# POWER.net
KiCad netlist of a schematic drawn in Altium Designer
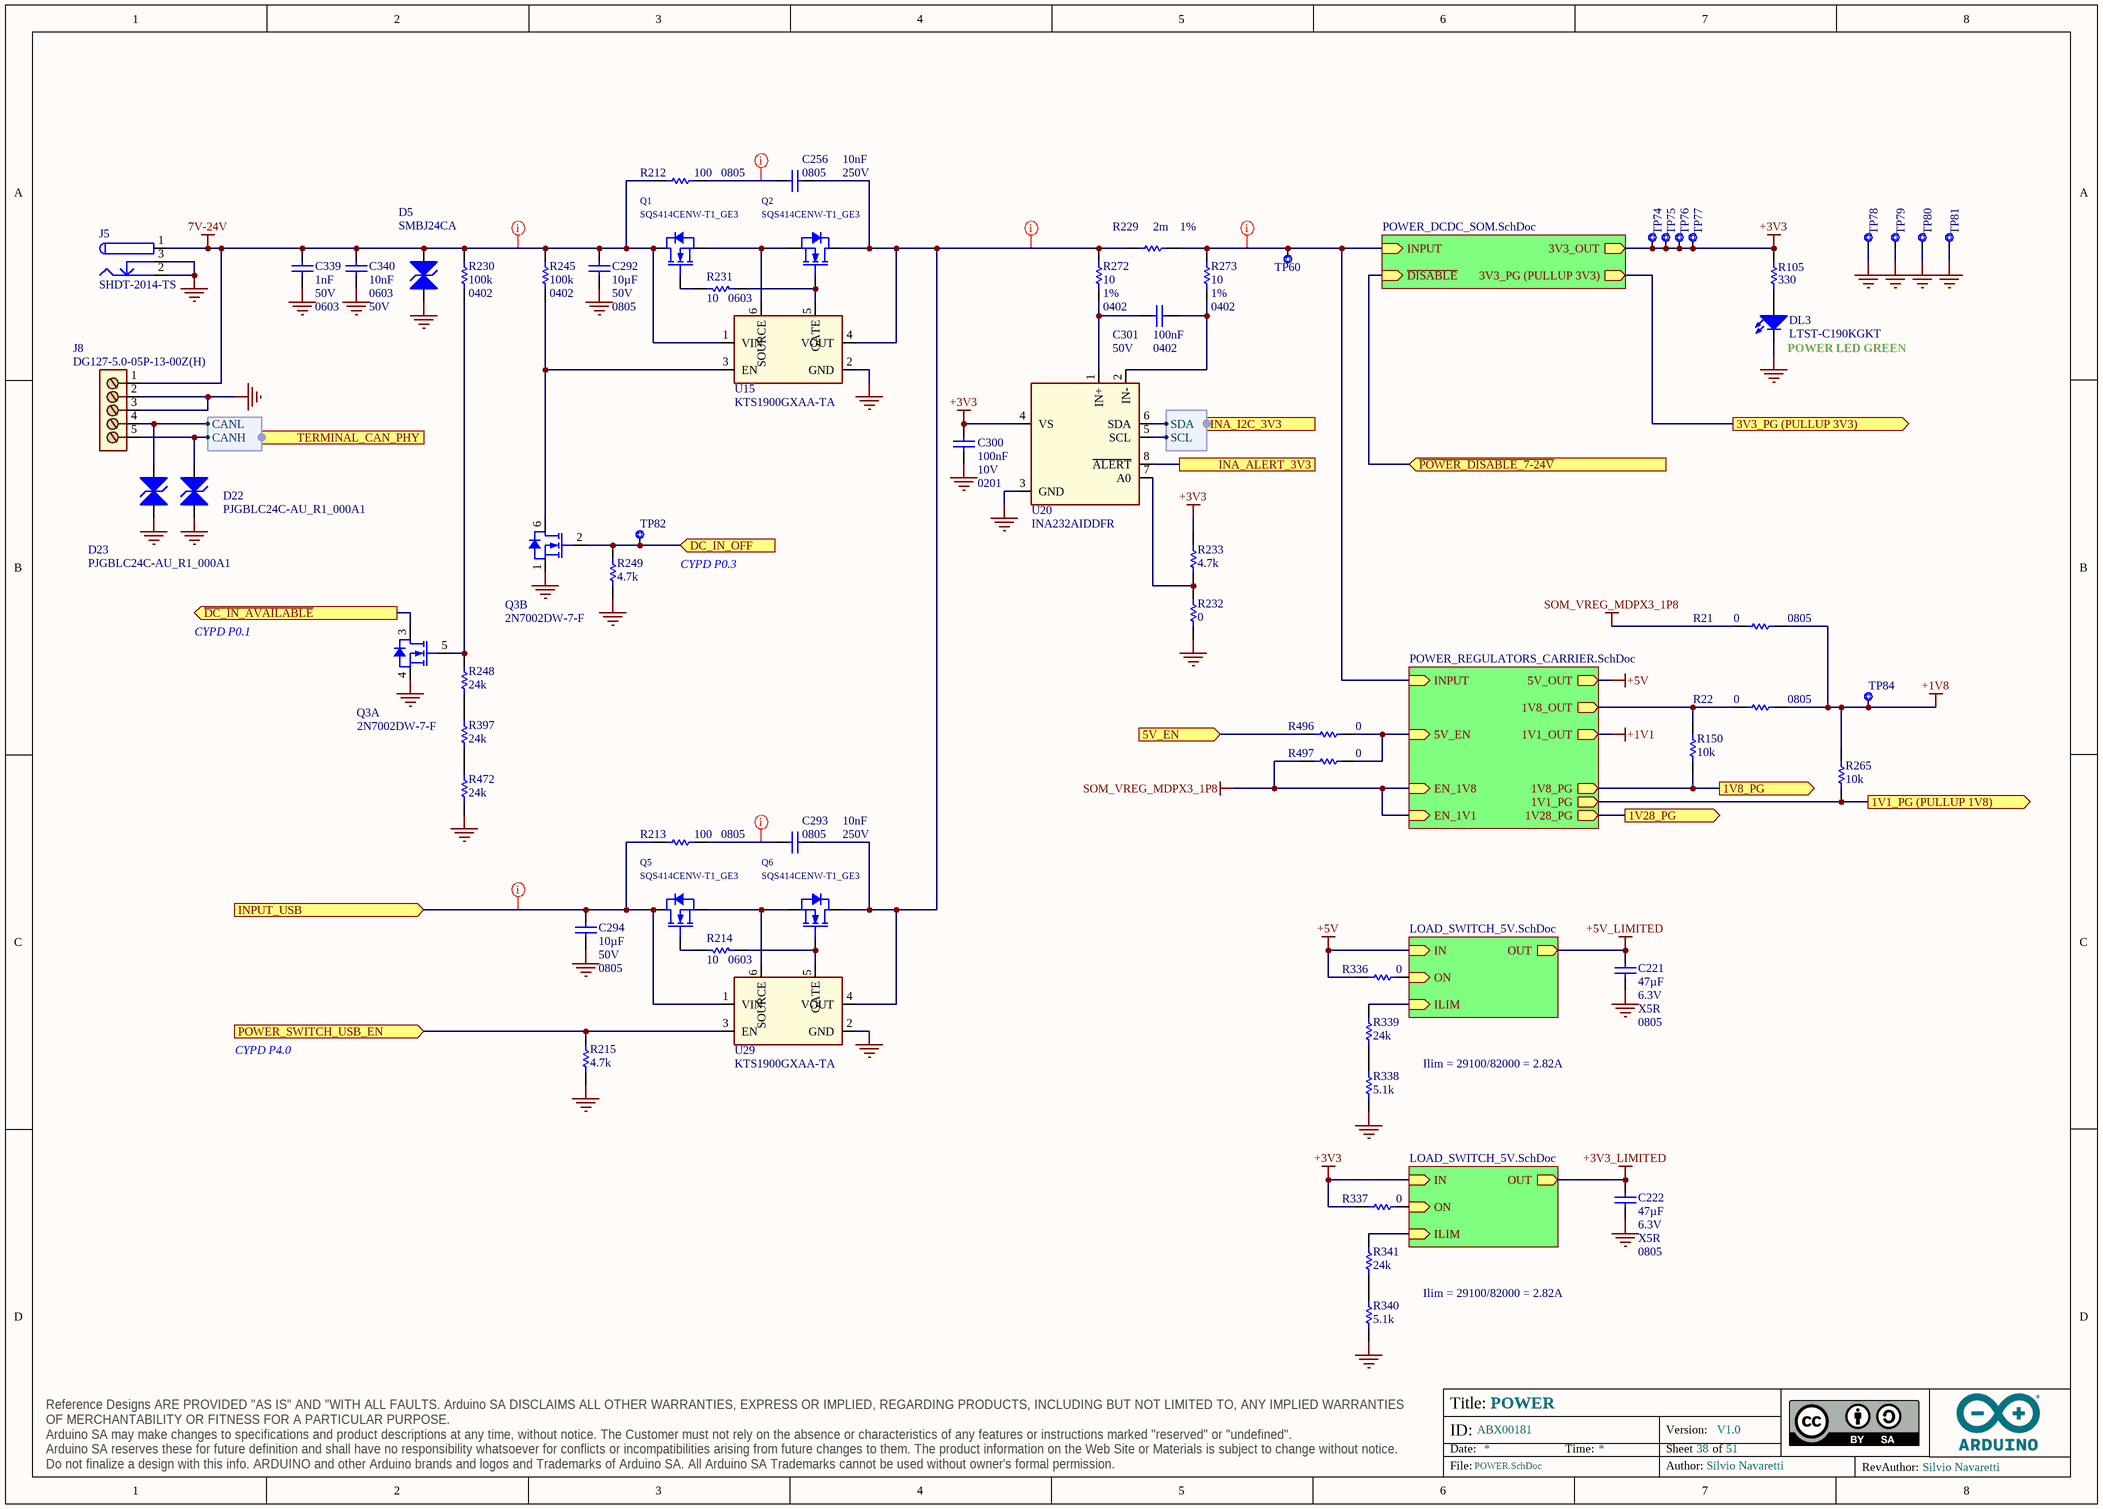
[diagram p0: POWER.SchDoc]

(export (version "E")
  (design (tool "Eeschema 10.0.6"))
  (components
    (comp (ref "C221")
      (value "47µF")
      (footprint "CAP-0805")
      (description "CAP CHIP 0805 47uF 20% 6.3V X5R")
      (fields
        (field (name "VOLTAGE") "6.3V")
        (field (name "DIELECTRIC") "X5R")
        (field (name "TOLERANCE") "20%")
        (field (name "CASE CODE (IMPERIAL)") "0805")
        (field (name "MANUFACTURER") "KEMET")
      )
      (libsource (lib "Clean") (part "CAP"))
    )
    (comp (ref "C222")
      (value "47µF")
      (footprint "CAP-0805")
      (description "CAP CHIP 0805 47uF 20% 6.3V X5R")
      (fields
        (field (name "VOLTAGE") "6.3V")
        (field (name "DIELECTRIC") "X5R")
        (field (name "TOLERANCE") "20%")
        (field (name "CASE CODE (IMPERIAL)") "0805")
        (field (name "MANUFACTURER") "KEMET")
      )
      (libsource (lib "Clean") (part "CAP"))
    )
    (comp (ref "C256")
      (value "10nF")
      (footprint "CAP-0805")
      (description "CAP CHIP 0805 10nF 250V X7R")
      (fields
        (field (name "CASE CODE (IMPERIAL)") "0805")
        (field (name "PART NUMBER") "GRM21BR72E103KW03L")
        (field (name "TOLERANCE") "10%")
        (field (name "VOLTAGE") "250V")
      )
      (libsource (lib "Clean") (part "CAP"))
    )
    (comp (ref "C292")
      (value "10µF")
      (footprint "CAP-0805")
      (description "CAP CHIP 0805 10uF 20% 50V X5R")
      (fields
        (field (name "VOLTAGE") "50V")
        (field (name "PART NUMBER") "GRM21BR61H106ME43L")
        (field (name "CASE CODE (IMPERIAL)") "0805")
        (field (name "MANUFACTURER") "Murata Electronics")
      )
      (libsource (lib "Clean") (part "CAP"))
    )
    (comp (ref "C293")
      (value "10nF")
      (footprint "CAP-0805")
      (description "CAP CHIP 0805 10nF 250V X7R")
      (fields
        (field (name "CASE CODE (IMPERIAL)") "0805")
        (field (name "PART NUMBER") "GRM21BR72E103KW03L")
        (field (name "TOLERANCE") "10%")
        (field (name "VOLTAGE") "250V")
      )
      (libsource (lib "Clean") (part "CAP"))
    )
    (comp (ref "C294")
      (value "10µF")
      (footprint "CAP-0805")
      (description "CAP CHIP 0805 10uF 20% 50V X5R")
      (fields
        (field (name "VOLTAGE") "50V")
        (field (name "PART NUMBER") "GRM21BR61H106ME43L")
        (field (name "CASE CODE (IMPERIAL)") "0805")
        (field (name "MANUFACTURER") "Murata Electronics")
      )
      (libsource (lib "Clean") (part "CAP"))
    )
    (comp (ref "C300")
      (value "100nF")
      (footprint "CAP-0201")
      (description "CAP CHIP 0201 100nF 10% 10V X5R")
      (fields
        (field (name "PART NUMBER") "CL03A104KP3NNNC")
        (field (name "MANUFACTURER") "Samsung Electro-Mechanics")
        (field (name "VOLTAGE") "10V")
        (field (name "CASE CODE (IMPERIAL)") "0201")
      )
      (libsource (lib "Clean") (part "CAP"))
    )
    (comp (ref "C301")
      (value "100nF")
      (footprint "CAP-0402")
      (description "CAP CHIP 0402 100nF 10% 50V X5R")
      (fields
        (field (name "MANUFACTURER") "Murata")
        (field (name "PART NUMBER") "GRM155R61H104KE19D")
        (field (name "VOLTAGE") "50V")
        (field (name "CASE CODE (IMPERIAL)") "0402")
      )
      (libsource (lib "Clean") (part "CAP"))
    )
    (comp (ref "C339")
      (value "1nF")
      (footprint "CAP-0603")
      (description "CAP CHIP 0603 1nF 10% 50V X7R")
      (fields
        (field (name "VOLTAGE") "50V")
        (field (name "TOLERANCE") "10%")
        (field (name "PART NUMBER") "CL10B102KB8WPNC")
        (field (name "CASE CODE (IMPERIAL)") "0603")
      )
      (libsource (lib "Clean") (part "CAP"))
    )
    (comp (ref "C340")
      (value "10nF")
      (footprint "CAP-0603")
      (description "CAP CHIP 0603 10nF 10% 50V X7R")
      (fields
        (field (name "CASE CODE (IMPERIAL)") "0603")
        (field (name "PART NUMBER") "0603B103K500CT")
        (field (name "TOLERANCE") "10%")
        (field (name "VOLTAGE") "50V")
      )
      (libsource (lib "Clean") (part "CAP"))
    )
    (comp (ref "D5")
      (value "SMBJ24CA")
      (footprint "SMB_NOPOLARITY")
      (description "TVS BIDIRECTIONAL SMD Vr 24V, Vbr min 26.7V, 600W, SMB")
      (fields (field (name "MANUFACTURER") "Littlefuse"))
      (libsource (lib "Clean") (part "Diode TVS"))
    )
    (comp (ref "D22")
      (value "PJGBLC24C-AU_R1_000A1")
      (footprint "SOD323 NO POLARITY")
      (description "TVS BIDIRECTIONAL SMD Vr 24V, Vbr min 27.27V, 350W, SOD-323")
      (libsource (lib "Clean") (part "Diode TVS"))
    )
    (comp (ref "D23")
      (value "PJGBLC24C-AU_R1_000A1")
      (footprint "SOD323 NO POLARITY")
      (description "TVS BIDIRECTIONAL SMD Vr 24V, Vbr min 27.27V, 350W, SOD-323")
      (libsource (lib "Clean") (part "Diode TVS"))
    )
    (comp (ref "DL3")
      (value "LTST-C190KGKT")
      (footprint "LEDC1608X80N-AK")
      (description "LED SMD 0603 GREEN/568 15mcd 120^")
      (fields (field (name "MANUFACTURER") "Liteon"))
      (libsource (lib "Clean") (part "LED"))
    )
    (comp (ref "J5")
      (value "SHDT-2014-TS")
      (footprint "SHDT-2014-TS")
      (description "CONN PWR JACK TH 2.1X5.5mm 1.6mm PCB")
      (fields (field (name "MANUFACTURER") "POWERWAY"))
      (libsource (lib "Clean") (part "SHDT-2014-TS"))
    )
    (comp (ref "J8")
      (value "DG127-5.0-05P-13-00Z(H)")
      (footprint "DG127-5.0-05P-13-00Z(H)")
      (description "CONN SCREW TERMINAL 5 POS pitch 5mm height 13.6mm BLACK")
      (fields (field (name "MANUFACTURER") "Degson"))
      (libsource (lib "Clean") (part "DG127-5.0-05P-13-00Z(H)"))
    )
    (comp (ref "Q1")
      (value "SQS414CENW-T1_GE3")
      (footprint "SQS414CENW-T1_GE3")
      (description "MOSFET N-CH 60V 18A PowerPAK 1212-8W 3.3x3.3mm")
      (fields (field (name "MANUFACTURER") "Vishay"))
      (libsource (lib "Clean") (part "SQS414CENW-T1_GE3"))
    )
    (comp (ref "Q2")
      (value "SQS414CENW-T1_GE3")
      (footprint "SQS414CENW-T1_GE3")
      (description "MOSFET N-CH 60V 18A PowerPAK 1212-8W 3.3x3.3mm")
      (fields (field (name "MANUFACTURER") "Vishay"))
      (libsource (lib "Clean") (part "SQS414CENW-T1_GE3"))
    )
    (comp (ref "Q3")
      (value "2N7002DW-7-F")
      (footprint "SOT363")
      (description "MOSFET 2N-CH 60V 0.32A SOT363")
      (fields (field (name "MANUFACTURER") "Diodes Inc.") (field (name "PART NUMBER") "2N7002DW-7-F"))
      (libsource (lib "Clean") (part "2N7002DW-7-F"))
    )
    (comp (ref "Q5")
      (value "SQS414CENW-T1_GE3")
      (footprint "SQS414CENW-T1_GE3")
      (description "MOSFET N-CH 60V 18A PowerPAK 1212-8W 3.3x3.3mm")
      (fields (field (name "MANUFACTURER") "Vishay"))
      (libsource (lib "Clean") (part "SQS414CENW-T1_GE3"))
    )
    (comp (ref "Q6")
      (value "SQS414CENW-T1_GE3")
      (footprint "SQS414CENW-T1_GE3")
      (description "MOSFET N-CH 60V 18A PowerPAK 1212-8W 3.3x3.3mm")
      (fields (field (name "MANUFACTURER") "Vishay"))
      (libsource (lib "Clean") (part "SQS414CENW-T1_GE3"))
    )
    (comp (ref "R21")
      (value "0")
      (footprint "RES-0805")
      (description "RES CHIP 0805 0R 1% 1/8W")
      (fields
        (field (name "POWER") "125mW")
        (field (name "PART NUMBER") "RC0805FR-070RL")
        (field (name "CASE CODE (IMPERIAL)") "0805")
      )
      (libsource (lib "Clean") (part "RES"))
    )
    (comp (ref "R22")
      (value "0")
      (footprint "RES-0805")
      (description "RES CHIP 0805 0R 1% 1/8W")
      (fields
        (field (name "POWER") "125mW")
        (field (name "PART NUMBER") "RC0805FR-070RL")
        (field (name "CASE CODE (IMPERIAL)") "0805")
      )
      (libsource (lib "Clean") (part "RES"))
    )
    (comp (ref "R105")
      (value "330")
      (footprint "RES-0201")
      (description "RES CHIP 0201 330R 1% 1/20W")
      (fields (field (name "MANUFACTURER") "Yageo") (field (name "POWER") "50mW"))
      (libsource (lib "Clean") (part "RES"))
    )
    (comp (ref "R150")
      (value "10k")
      (footprint "RES-0201")
      (description "RES CHIP 0201 10k 1% 1/20W")
      (fields (field (name "POWER") "50mW") (field (name "TOLERANCE") "1%"))
      (libsource (lib "Clean") (part "RES"))
    )
    (comp (ref "R212")
      (value "100")
      (footprint "RES-0805")
      (description "RES CHIP 0805 100R 1% 1/8W 100ppm")
      (fields
        (field (name "PART NUMBER") "RC0805FR-07100RL")
        (field (name "TOLERANCE") "1%")
        (field (name "CASE CODE (IMPERIAL)") "0805")
      )
      (libsource (lib "Clean") (part "RES"))
    )
    (comp (ref "R213")
      (value "100")
      (footprint "RES-0805")
      (description "RES CHIP 0805 100R 1% 1/8W 100ppm")
      (fields
        (field (name "PART NUMBER") "RC0805FR-07100RL")
        (field (name "TOLERANCE") "1%")
        (field (name "CASE CODE (IMPERIAL)") "0805")
      )
      (libsource (lib "Clean") (part "RES"))
    )
    (comp (ref "R214")
      (value "10")
      (footprint "RES-0603")
      (description "RES CHIP 0603 10R 1% 1/10W")
      (fields
        (field (name "PART NUMBER") "CRCW060310R0FKEAC")
        (field (name "MANUFACTURER") "Vishay")
        (field (name "CASE CODE (IMPERIAL)") "0603")
      )
      (libsource (lib "Clean") (part "RES"))
    )
    (comp (ref "R215")
      (value "4.7k")
      (footprint "RES-0201")
      (description "RES CHIP 0201 4k7 1% 1/20W")
      (fields (field (name "POWER") "50mW") (field (name "PART NUMBER") "RC0201FR-074K7L"))
      (libsource (lib "Clean") (part "RES"))
    )
    (comp (ref "R229")
      (value "2m")
      (footprint "RES-0805")
      (description "RES CHIP 0805 2mR 1% 1/2W")
      (fields
        (field (name "PART NUMBER") "PMR10EZPFV2L00")
        (field (name "POWER") "500mW")
        (field (name "TOLERANCE") "1%")
      )
      (libsource (lib "Clean") (part "RES"))
    )
    (comp (ref "R230")
      (value "100k")
      (footprint "RES-0402")
      (description "RES CHIP 0402 100k 1% 1/16W")
      (fields
        (field (name "POWER") "62.5mW")
        (field (name "TOLERANCE") "1%")
        (field (name "CASE CODE (IMPERIAL)") "0402")
      )
      (libsource (lib "Clean") (part "RES"))
    )
    (comp (ref "R231")
      (value "10")
      (footprint "RES-0603")
      (description "RES CHIP 0603 10R 1% 1/10W")
      (fields
        (field (name "PART NUMBER") "CRCW060310R0FKEAC")
        (field (name "MANUFACTURER") "Vishay")
        (field (name "CASE CODE (IMPERIAL)") "0603")
      )
      (libsource (lib "Clean") (part "RES"))
    )
    (comp (ref "R232")
      (value "0")
      (footprint "RES-0201")
      (description "RES CHIP 0201 0R")
      (fields (field (name "MANUFACTURER") "Vishay") (field (name "PART NUMBER") "CRCW02010000Z0ED"))
      (libsource (lib "Clean") (part "RES"))
    )
    (comp (ref "R233")
      (value "4.7k")
      (footprint "RES-0201")
      (description "RES CHIP 0201 4k7 1% 1/20W")
      (fields (field (name "POWER") "50mW") (field (name "PART NUMBER") "RC0201FR-074K7L"))
      (libsource (lib "Clean") (part "RES"))
    )
    (comp (ref "R245")
      (value "100k")
      (footprint "RES-0402")
      (description "RES CHIP 0402 100k 1% 1/16W")
      (fields
        (field (name "POWER") "62.5mW")
        (field (name "TOLERANCE") "1%")
        (field (name "CASE CODE (IMPERIAL)") "0402")
      )
      (libsource (lib "Clean") (part "RES"))
    )
    (comp (ref "R248")
      (value "24k")
      (footprint "RES-0201")
      (description "RES CHIP 0201 24k 1% 1/20W")
      (fields (field (name "POWER") "50mW") (field (name "PART NUMBER") "RC0201FR-0724KL"))
      (libsource (lib "Clean") (part "RES"))
    )
    (comp (ref "R249")
      (value "4.7k")
      (footprint "RES-0201")
      (description "RES CHIP 0201 4k7 1% 1/20W")
      (fields (field (name "POWER") "50mW") (field (name "PART NUMBER") "RC0201FR-074K7L"))
      (libsource (lib "Clean") (part "RES"))
    )
    (comp (ref "R265")
      (value "10k")
      (footprint "RES-0201")
      (description "RES CHIP 0201 10k 1% 1/20W")
      (fields (field (name "POWER") "50mW") (field (name "TOLERANCE") "1%"))
      (libsource (lib "Clean") (part "RES"))
    )
    (comp (ref "R272")
      (value "10")
      (footprint "RES-0402")
      (description "RES CHIP 0402 10R 1% 1/16W")
      (fields
        (field (name "PART NUMBER") "RC0402FR-0710RL")
        (field (name "TOLERANCE") "1%")
        (field (name "CASE CODE (IMPERIAL)") "0402")
        (field (name "POWER") "62.5mW")
      )
      (libsource (lib "Clean") (part "RES"))
    )
    (comp (ref "R273")
      (value "10")
      (footprint "RES-0402")
      (description "RES CHIP 0402 10R 1% 1/16W")
      (fields
        (field (name "PART NUMBER") "RC0402FR-0710RL")
        (field (name "TOLERANCE") "1%")
        (field (name "CASE CODE (IMPERIAL)") "0402")
        (field (name "POWER") "62.5mW")
      )
      (libsource (lib "Clean") (part "RES"))
    )
    (comp (ref "R336")
      (value "0")
      (footprint "RES-0201")
      (description "RES CHIP 0201 0R")
      (fields (field (name "MANUFACTURER") "Vishay") (field (name "PART NUMBER") "CRCW02010000Z0ED"))
      (libsource (lib "Clean") (part "RES"))
    )
    (comp (ref "R337")
      (value "0")
      (footprint "RES-0201")
      (description "RES CHIP 0201 0R")
      (fields (field (name "MANUFACTURER") "Vishay") (field (name "PART NUMBER") "CRCW02010000Z0ED"))
      (libsource (lib "Clean") (part "RES"))
    )
    (comp (ref "R338")
      (value "5.1k")
      (footprint "RES-0201")
      (description "RES CHIP 0201 5k1 1% 1/20W")
      (fields (field (name "MANUFACTURER") "Panasonic") (field (name "PART NUMBER") "ERJ-1GNF5101C"))
      (libsource (lib "Clean") (part "RES"))
    )
    (comp (ref "R339")
      (value "24k")
      (footprint "RES-0201")
      (description "RES CHIP 0201 24k 1% 1/20W")
      (fields (field (name "MANUFACTURER") "YAGEO") (field (name "PART NUMBER") "RC0201FR-0724KL"))
      (libsource (lib "Clean") (part "RES"))
    )
    (comp (ref "R340")
      (value "5.1k")
      (footprint "RES-0201")
      (description "RES CHIP 0201 5k1 1% 1/20W")
      (fields (field (name "MANUFACTURER") "Panasonic") (field (name "PART NUMBER") "ERJ-1GNF5101C"))
      (libsource (lib "Clean") (part "RES"))
    )
    (comp (ref "R341")
      (value "24k")
      (footprint "RES-0201")
      (description "RES CHIP 0201 24k 1% 1/20W")
      (fields (field (name "MANUFACTURER") "YAGEO") (field (name "PART NUMBER") "RC0201FR-0724KL"))
      (libsource (lib "Clean") (part "RES"))
    )
    (comp (ref "R397")
      (value "24k")
      (footprint "RES-0201")
      (description "RES CHIP 0201 24k 1% 1/20W")
      (fields (field (name "POWER") "50mW") (field (name "PART NUMBER") "RC0201FR-0724KL"))
      (libsource (lib "Clean") (part "RES"))
    )
    (comp (ref "R472")
      (value "24k")
      (footprint "RES-0201")
      (description "RES CHIP 0201 24k 1% 1/20W")
      (fields (field (name "POWER") "50mW") (field (name "PART NUMBER") "RC0201FR-0724KL"))
      (libsource (lib "Clean") (part "RES"))
    )
    (comp (ref "R496")
      (value "0")
      (footprint "RES-0201")
      (description "RES CHIP 0201 0R")
      (fields (field (name "MANUFACTURER") "Vishay") (field (name "PART NUMBER") "CRCW02010000Z0ED"))
      (libsource (lib "Clean") (part "RES"))
    )
    (comp (ref "R497")
      (value "0")
      (footprint "RES-0201")
      (description "RES CHIP 0201 0R")
      (fields (field (name "MANUFACTURER") "Vishay") (field (name "PART NUMBER") "CRCW02010000Z0ED"))
      (libsource (lib "Clean") (part "RES"))
    )
    (comp (ref "TP60")
      (value "Test point 1.00mm")
      (footprint "TP-1.00MM")
      (fields (field (name "PART NUMBER") "This is not a component"))
      (libsource (lib "Clean") (part "TESTPOINT"))
    )
    (comp (ref "TP74")
      (value "Test point 1.00mm")
      (footprint "TP-1.00MM")
      (fields (field (name "PART NUMBER") "This is not a component"))
      (libsource (lib "Clean") (part "TESTPOINT"))
    )
    (comp (ref "TP75")
      (value "Test point 1.00mm")
      (footprint "TP-1.00MM")
      (fields (field (name "PART NUMBER") "This is not a component"))
      (libsource (lib "Clean") (part "TESTPOINT"))
    )
    (comp (ref "TP76")
      (value "Test point 1.00mm")
      (footprint "TP-1.00MM")
      (fields (field (name "PART NUMBER") "This is not a component"))
      (libsource (lib "Clean") (part "TESTPOINT"))
    )
    (comp (ref "TP77")
      (value "Test point 1.00mm")
      (footprint "TP-1.00MM")
      (fields (field (name "PART NUMBER") "This is not a component"))
      (libsource (lib "Clean") (part "TESTPOINT"))
    )
    (comp (ref "TP78")
      (value "Test point 1.00mm")
      (footprint "TP-1.00MM")
      (fields (field (name "PART NUMBER") "This is not a component"))
      (libsource (lib "Clean") (part "TESTPOINT"))
    )
    (comp (ref "TP79")
      (value "Test point 1.00mm")
      (footprint "TP-1.00MM")
      (fields (field (name "PART NUMBER") "This is not a component"))
      (libsource (lib "Clean") (part "TESTPOINT"))
    )
    (comp (ref "TP80")
      (value "Test point 1.00mm")
      (footprint "TP-1.00MM")
      (fields (field (name "PART NUMBER") "This is not a component"))
      (libsource (lib "Clean") (part "TESTPOINT"))
    )
    (comp (ref "TP81")
      (value "Test point 1.00mm")
      (footprint "TP-1.00MM")
      (fields (field (name "PART NUMBER") "This is not a component"))
      (libsource (lib "Clean") (part "TESTPOINT"))
    )
    (comp (ref "TP82")
      (value "Test point 1.00mm")
      (footprint "TP-1.00MM")
      (fields (field (name "PART NUMBER") "This is not a component"))
      (libsource (lib "Clean") (part "TESTPOINT"))
    )
    (comp (ref "TP84")
      (value "Test point 1.00mm")
      (footprint "TP-1.00MM")
      (fields (field (name "PART NUMBER") "This is not a component"))
      (libsource (lib "Clean") (part "TESTPOINT"))
    )
    (comp (ref "U15")
      (value "KTS1900GXAA-TA")
      (footprint "SOT23-6 PITCH 0.95")
      (fields (field (name "MANUFACTURER") "Kinetic Technology"))
      (libsource (lib "Clean") (part "KTS1900GXAA-TA-Symbol-1"))
    )
    (comp (ref "U20")
      (value "INA232AIDDFR")
      (footprint "TI DDF SOT23-THIN 8 pin 1.6x2.9x1.1 mm heigth")
      (description "IC MONITOR PWR/CURR/VOLT 16bit ADC I2C SOT23-THIN8 1.6x2.9x1.1 mm")
      (fields (field (name "MANUFACTURER") "Texas Instruments"))
      (libsource (lib "Clean") (part "INA232AIDDFR"))
    )
    (comp (ref "U29")
      (value "KTS1900GXAA-TA")
      (footprint "SOT23-6 PITCH 0.95")
      (fields (field (name "MANUFACTURER") "Kinetic Technology"))
      (libsource (lib "Clean") (part "KTS1900GXAA-TA-Symbol-1"))
    )
  )
  (nets
    (net (code "4") (name "+1V8") (class "Default")
      (node (ref "R21") (pin "2") (pinfunction "2_2") (pintype "passive"))
      (node (ref "R22") (pin "2") (pinfunction "2_2") (pintype "passive"))
      (node (ref "R265") (pin "1") (pinfunction "1_1") (pintype "passive"))
      (node (ref "TP84") (pin "X") (pinfunction "X_X") (pintype "passive"))
    )
    (net (code "5") (name "+3V3") (class "Default")
      (node (ref "C300") (pin "2") (pinfunction "2_2") (pintype "passive"))
      (node (ref "R105") (pin "2") (pinfunction "2_2") (pintype "passive"))
      (node (ref "R233") (pin "1") (pinfunction "1_1") (pintype "passive"))
      (node (ref "R337") (pin "1") (pinfunction "1_1") (pintype "passive"))
      (node (ref "TP74") (pin "X") (pinfunction "X_X") (pintype "passive"))
      (node (ref "TP75") (pin "X") (pinfunction "X_X") (pintype "passive"))
      (node (ref "TP76") (pin "X") (pinfunction "X_X") (pintype "passive"))
      (node (ref "TP77") (pin "X") (pinfunction "X_X") (pintype "passive"))
      (node (ref "U20") (pin "4") (pinfunction "VS_4") (pintype "passive"))
    )
    (net (code "6") (name "+3V3_LIMITED") (class "Default")
      (node (ref "C222") (pin "2") (pinfunction "2_2") (pintype "passive"))
    )
    (net (code "7") (name "+5V") (class "Default")
      (node (ref "R336") (pin "1") (pinfunction "1_1") (pintype "passive"))
    )
    (net (code "8") (name "+5V_LIMITED") (class "Default")
      (node (ref "C221") (pin "2") (pinfunction "2_2") (pintype "passive"))
    )
    (net (code "9") (name "/1V1_PG (PULLUP 1V8)") (class "Default")
      (node (ref "R265") (pin "2") (pinfunction "2_2") (pintype "passive"))
    )
    (net (code "10") (name "/1V8_OUT") (class "Default")
      (node (ref "R150") (pin "1") (pinfunction "1_1") (pintype "passive"))
      (node (ref "R22") (pin "1") (pinfunction "1_1") (pintype "passive"))
    )
    (net (code "11") (name "/1V8_PG") (class "Default")
      (node (ref "R150") (pin "2") (pinfunction "2_2") (pintype "passive"))
    )
    (net (code "14") (name "/5V_EN") (class "Default")
      (node (ref "R496") (pin "2") (pinfunction "2_2") (pintype "passive"))
    )
    (net (code "15") (name "/5V_EN_1") (class "Default")
      (node (ref "R496") (pin "1") (pinfunction "1_1") (pintype "passive"))
      (node (ref "R497") (pin "1") (pinfunction "1_1") (pintype "passive"))
    )
    (net (code "16") (name "/DC_IN_OFF") (class "Default")
      (node (ref "Q3") (pin "2") (pinfunction "G_2") (pintype "passive"))
      (node (ref "R249") (pin "1") (pinfunction "1_1") (pintype "passive"))
      (node (ref "TP82") (pin "X") (pinfunction "X_X") (pintype "passive"))
    )
    (net (code "17") (name "/ILIM") (class "Default")
      (node (ref "R339") (pin "2") (pinfunction "2_2") (pintype "passive"))
    )
    (net (code "18") (name "/ILIM_1") (class "Default")
      (node (ref "R341") (pin "2") (pinfunction "2_2") (pintype "passive"))
    )
    (net (code "19") (name "/INA_ALERT_3V3") (class "Default")
      (node (ref "U20") (pin "8") (pinfunction "~{ALERT}_8") (pintype "passive"))
    )
    (net (code "20") (name "/INPUT") (class "Default")
      (node (ref "R229") (pin "2") (pinfunction "2_2") (pintype "passive"))
      (node (ref "R273") (pin "2") (pinfunction "2_2") (pintype "passive"))
      (node (ref "TP60") (pin "X") (pinfunction "X_X") (pintype "passive"))
    )
    (net (code "21") (name "/INPUT_USB") (class "Default")
      (node (ref "C294") (pin "2") (pinfunction "2_2") (pintype "passive"))
      (node (ref "Q5") (pin "D") (pinfunction "D_D") (pintype "passive"))
      (node (ref "R213") (pin "2") (pinfunction "2_2") (pintype "passive"))
      (node (ref "U29") (pin "1") (pinfunction "VIN_1") (pintype "passive"))
    )
    (net (code "22") (name "/ON") (class "Default")
      (node (ref "R336") (pin "2") (pinfunction "2_2") (pintype "passive"))
    )
    (net (code "23") (name "/ON_1") (class "Default")
      (node (ref "R337") (pin "2") (pinfunction "2_2") (pintype "passive"))
    )
    (net (code "24") (name "/POWER_SWITCH_USB_EN") (class "Default")
      (node (ref "R215") (pin "1") (pinfunction "1_1") (pintype "passive"))
      (node (ref "U29") (pin "3") (pinfunction "EN_3") (pintype "passive"))
    )
    (net (code "27") (name "/~{DC_IN_AVAILABLE}") (class "Default")
      (node (ref "Q3") (pin "3") (pinfunction "D_3") (pintype "passive"))
    )
    (net (code "29") (name "7V-24V") (class "Default")
      (node (ref "C292") (pin "2") (pinfunction "2_2") (pintype "passive"))
      (node (ref "C339") (pin "1") (pinfunction "1_1") (pintype "passive"))
      (node (ref "C340") (pin "1") (pinfunction "1_1") (pintype "passive"))
      (node (ref "D5") (pin "2") (pinfunction "A2_2") (pintype "passive"))
      (node (ref "J5") (pin "1") (pinfunction "1_1") (pintype "power_in"))
      (node (ref "J8") (pin "1") (pinfunction "1_1") (pintype "passive"))
      (node (ref "Q1") (pin "D") (pinfunction "D_D") (pintype "passive"))
      (node (ref "R212") (pin "2") (pinfunction "2_2") (pintype "passive"))
      (node (ref "R230") (pin "1") (pinfunction "1_1") (pintype "passive"))
      (node (ref "R245") (pin "1") (pinfunction "1_1") (pintype "passive"))
      (node (ref "U15") (pin "1") (pinfunction "VIN_1") (pintype "passive"))
    )
    (net (code "30") (name "GND") (class "Default")
      (node (ref "C221") (pin "1") (pinfunction "1_1") (pintype "passive"))
      (node (ref "C222") (pin "1") (pinfunction "1_1") (pintype "passive"))
      (node (ref "C292") (pin "1") (pinfunction "1_1") (pintype "passive"))
      (node (ref "C294") (pin "1") (pinfunction "1_1") (pintype "passive"))
      (node (ref "C300") (pin "1") (pinfunction "1_1") (pintype "passive"))
      (node (ref "C339") (pin "2") (pinfunction "2_2") (pintype "passive"))
      (node (ref "C340") (pin "2") (pinfunction "2_2") (pintype "passive"))
      (node (ref "D22") (pin "1") (pinfunction "A1_1") (pintype "passive"))
      (node (ref "D23") (pin "1") (pinfunction "A1_1") (pintype "passive"))
      (node (ref "D5") (pin "1") (pinfunction "A1_1") (pintype "passive"))
      (node (ref "DL3") (pin "C") (pinfunction "C_C") (pintype "passive"))
      (node (ref "J5") (pin "2") (pinfunction "2_2") (pintype "power_in"))
      (node (ref "J5") (pin "3") (pinfunction "3_3") (pintype "power_in"))
      (node (ref "J8") (pin "2") (pinfunction "2_2") (pintype "passive"))
      (node (ref "J8") (pin "3") (pinfunction "3_3") (pintype "passive"))
      (node (ref "Q3") (pin "1") (pinfunction "S_1") (pintype "passive"))
      (node (ref "Q3") (pin "4") (pinfunction "S_4") (pintype "passive"))
      (node (ref "R215") (pin "2") (pinfunction "2_2") (pintype "passive"))
      (node (ref "R232") (pin "1") (pinfunction "1_1") (pintype "passive"))
      (node (ref "R249") (pin "2") (pinfunction "2_2") (pintype "passive"))
      (node (ref "R338") (pin "1") (pinfunction "1_1") (pintype "passive"))
      (node (ref "R340") (pin "1") (pinfunction "1_1") (pintype "passive"))
      (node (ref "R472") (pin "1") (pinfunction "1_1") (pintype "passive"))
      (node (ref "TP78") (pin "X") (pinfunction "X_X") (pintype "passive"))
      (node (ref "TP79") (pin "X") (pinfunction "X_X") (pintype "passive"))
      (node (ref "TP80") (pin "X") (pinfunction "X_X") (pintype "passive"))
      (node (ref "TP81") (pin "X") (pinfunction "X_X") (pintype "passive"))
      (node (ref "U15") (pin "2") (pinfunction "GND_2") (pintype "passive"))
      (node (ref "U20") (pin "3") (pinfunction "GND_3") (pintype "passive"))
      (node (ref "U29") (pin "2") (pinfunction "GND_2") (pintype "passive"))
    )
    (net (code "31") (name "Net-(C256-Pad1)") (class "Default")
      (node (ref "C256") (pin "1") (pinfunction "1_1") (pintype "passive"))
      (node (ref "R212") (pin "1") (pinfunction "1_1") (pintype "passive"))
    )
    (net (code "32") (name "Net-(C293-Pad1)") (class "Default")
      (node (ref "C293") (pin "1") (pinfunction "1_1") (pintype "passive"))
      (node (ref "R213") (pin "1") (pinfunction "1_1") (pintype "passive"))
    )
    (net (code "33") (name "Net-(D22-A2)") (class "Default")
      (node (ref "D22") (pin "2") (pinfunction "A2_2") (pintype "passive"))
      (node (ref "J8") (pin "5") (pinfunction "5_5") (pintype "passive"))
    )
    (net (code "34") (name "Net-(D23-A2)") (class "Default")
      (node (ref "D23") (pin "2") (pinfunction "A2_2") (pintype "passive"))
      (node (ref "J8") (pin "4") (pinfunction "4_4") (pintype "passive"))
    )
    (net (code "35") (name "Net-(DL3-PadA)") (class "Default")
      (node (ref "DL3") (pin "A") (pinfunction "A_A") (pintype "passive"))
      (node (ref "R105") (pin "1") (pinfunction "1_1") (pintype "passive"))
    )
    (net (code "36") (name "Net-(Q1-PadG)") (class "Default")
      (node (ref "Q1") (pin "G") (pinfunction "G_G") (pintype "passive"))
      (node (ref "R231") (pin "2") (pinfunction "2_2") (pintype "passive"))
    )
    (net (code "37") (name "Net-(Q3A-G)") (class "Default")
      (node (ref "Q3") (pin "5") (pinfunction "G_5") (pintype "passive"))
      (node (ref "R230") (pin "2") (pinfunction "2_2") (pintype "passive"))
      (node (ref "R248") (pin "2") (pinfunction "2_2") (pintype "passive"))
    )
    (net (code "38") (name "Net-(Q3B-D)") (class "Default")
      (node (ref "Q3") (pin "6") (pinfunction "D_6") (pintype "passive"))
      (node (ref "R245") (pin "2") (pinfunction "2_2") (pintype "passive"))
      (node (ref "U15") (pin "3") (pinfunction "EN_3") (pintype "passive"))
    )
    (net (code "39") (name "Net-(Q5-PadG)") (class "Default")
      (node (ref "Q5") (pin "G") (pinfunction "G_G") (pintype "passive"))
      (node (ref "R214") (pin "2") (pinfunction "2_2") (pintype "passive"))
    )
    (net (code "40") (name "Net-(R248-Pad1)") (class "Default")
      (node (ref "R248") (pin "1") (pinfunction "1_1") (pintype "passive"))
      (node (ref "R397") (pin "2") (pinfunction "2_2") (pintype "passive"))
    )
    (net (code "41") (name "Net-(R338-Pad2)") (class "Default")
      (node (ref "R338") (pin "2") (pinfunction "2_2") (pintype "passive"))
      (node (ref "R339") (pin "1") (pinfunction "1_1") (pintype "passive"))
    )
    (net (code "42") (name "Net-(R340-Pad2)") (class "Default")
      (node (ref "R340") (pin "2") (pinfunction "2_2") (pintype "passive"))
      (node (ref "R341") (pin "1") (pinfunction "1_1") (pintype "passive"))
    )
    (net (code "43") (name "Net-(R397-Pad1)") (class "Default")
      (node (ref "R397") (pin "1") (pinfunction "1_1") (pintype "passive"))
      (node (ref "R472") (pin "2") (pinfunction "2_2") (pintype "passive"))
    )
    (net (code "44") (name "Net-(U15-GATE)") (class "Default")
      (node (ref "Q2") (pin "G") (pinfunction "G_G") (pintype "passive"))
      (node (ref "R231") (pin "1") (pinfunction "1_1") (pintype "passive"))
      (node (ref "U15") (pin "5") (pinfunction "GATE_5") (pintype "passive"))
    )
    (net (code "45") (name "Net-(U15-SOURCE)") (class "Default")
      (node (ref "Q1") (pin "S") (pinfunction "S_S") (pintype "passive"))
      (node (ref "Q2") (pin "S") (pinfunction "S_S") (pintype "passive"))
      (node (ref "U15") (pin "6") (pinfunction "SOURCE_6") (pintype "passive"))
    )
    (net (code "46") (name "Net-(U15-VOUT)") (class "Default")
      (node (ref "C256") (pin "2") (pinfunction "2_2") (pintype "passive"))
      (node (ref "C293") (pin "2") (pinfunction "2_2") (pintype "passive"))
      (node (ref "Q2") (pin "D") (pinfunction "D_D") (pintype "passive"))
      (node (ref "Q6") (pin "D") (pinfunction "D_D") (pintype "passive"))
      (node (ref "R229") (pin "1") (pinfunction "1_1") (pintype "passive"))
      (node (ref "R272") (pin "2") (pinfunction "2_2") (pintype "passive"))
      (node (ref "U15") (pin "4") (pinfunction "VOUT_4") (pintype "passive"))
      (node (ref "U29") (pin "4") (pinfunction "VOUT_4") (pintype "passive"))
    )
    (net (code "47") (name "Net-(U20-A0)") (class "Default")
      (node (ref "R232") (pin "2") (pinfunction "2_2") (pintype "passive"))
      (node (ref "R233") (pin "2") (pinfunction "2_2") (pintype "passive"))
      (node (ref "U20") (pin "7") (pinfunction "A0_7") (pintype "passive"))
    )
    (net (code "48") (name "Net-(U20-IN+)") (class "Default")
      (node (ref "C301") (pin "1") (pinfunction "1_1") (pintype "passive"))
      (node (ref "R272") (pin "1") (pinfunction "1_1") (pintype "passive"))
      (node (ref "U20") (pin "1") (pinfunction "IN+_1") (pintype "passive"))
    )
    (net (code "49") (name "Net-(U20-IN-)") (class "Default")
      (node (ref "C301") (pin "2") (pinfunction "2_2") (pintype "passive"))
      (node (ref "R273") (pin "1") (pinfunction "1_1") (pintype "passive"))
      (node (ref "U20") (pin "2") (pinfunction "IN-_2") (pintype "passive"))
    )
    (net (code "50") (name "Net-(U29-GATE)") (class "Default")
      (node (ref "Q6") (pin "G") (pinfunction "G_G") (pintype "passive"))
      (node (ref "R214") (pin "1") (pinfunction "1_1") (pintype "passive"))
      (node (ref "U29") (pin "5") (pinfunction "GATE_5") (pintype "passive"))
    )
    (net (code "51") (name "Net-(U29-SOURCE)") (class "Default")
      (node (ref "Q5") (pin "S") (pinfunction "S_S") (pintype "passive"))
      (node (ref "Q6") (pin "S") (pinfunction "S_S") (pintype "passive"))
      (node (ref "U29") (pin "6") (pinfunction "SOURCE_6") (pintype "passive"))
    )
    (net (code "52") (name "SOM_VREG_MDPX3_1P8") (class "Default")
      (node (ref "R21") (pin "1") (pinfunction "1_1") (pintype "passive"))
      (node (ref "R497") (pin "2") (pinfunction "2_2") (pintype "passive"))
    )
    (net (code "53") (name "unconnected-(U20-SCL-Pad5)") (class "Default")
      (node (ref "U20") (pin "5") (pinfunction "SCL_5") (pintype "passive"))
    )
    (net (code "54") (name "unconnected-(U20-SDA-Pad6)") (class "Default")
      (node (ref "U20") (pin "6") (pinfunction "SDA_6") (pintype "passive"))
    )
  )
)
